# LPC_AP2_3_52.net
KiCad netlist of a schematic drawn in EAGLE
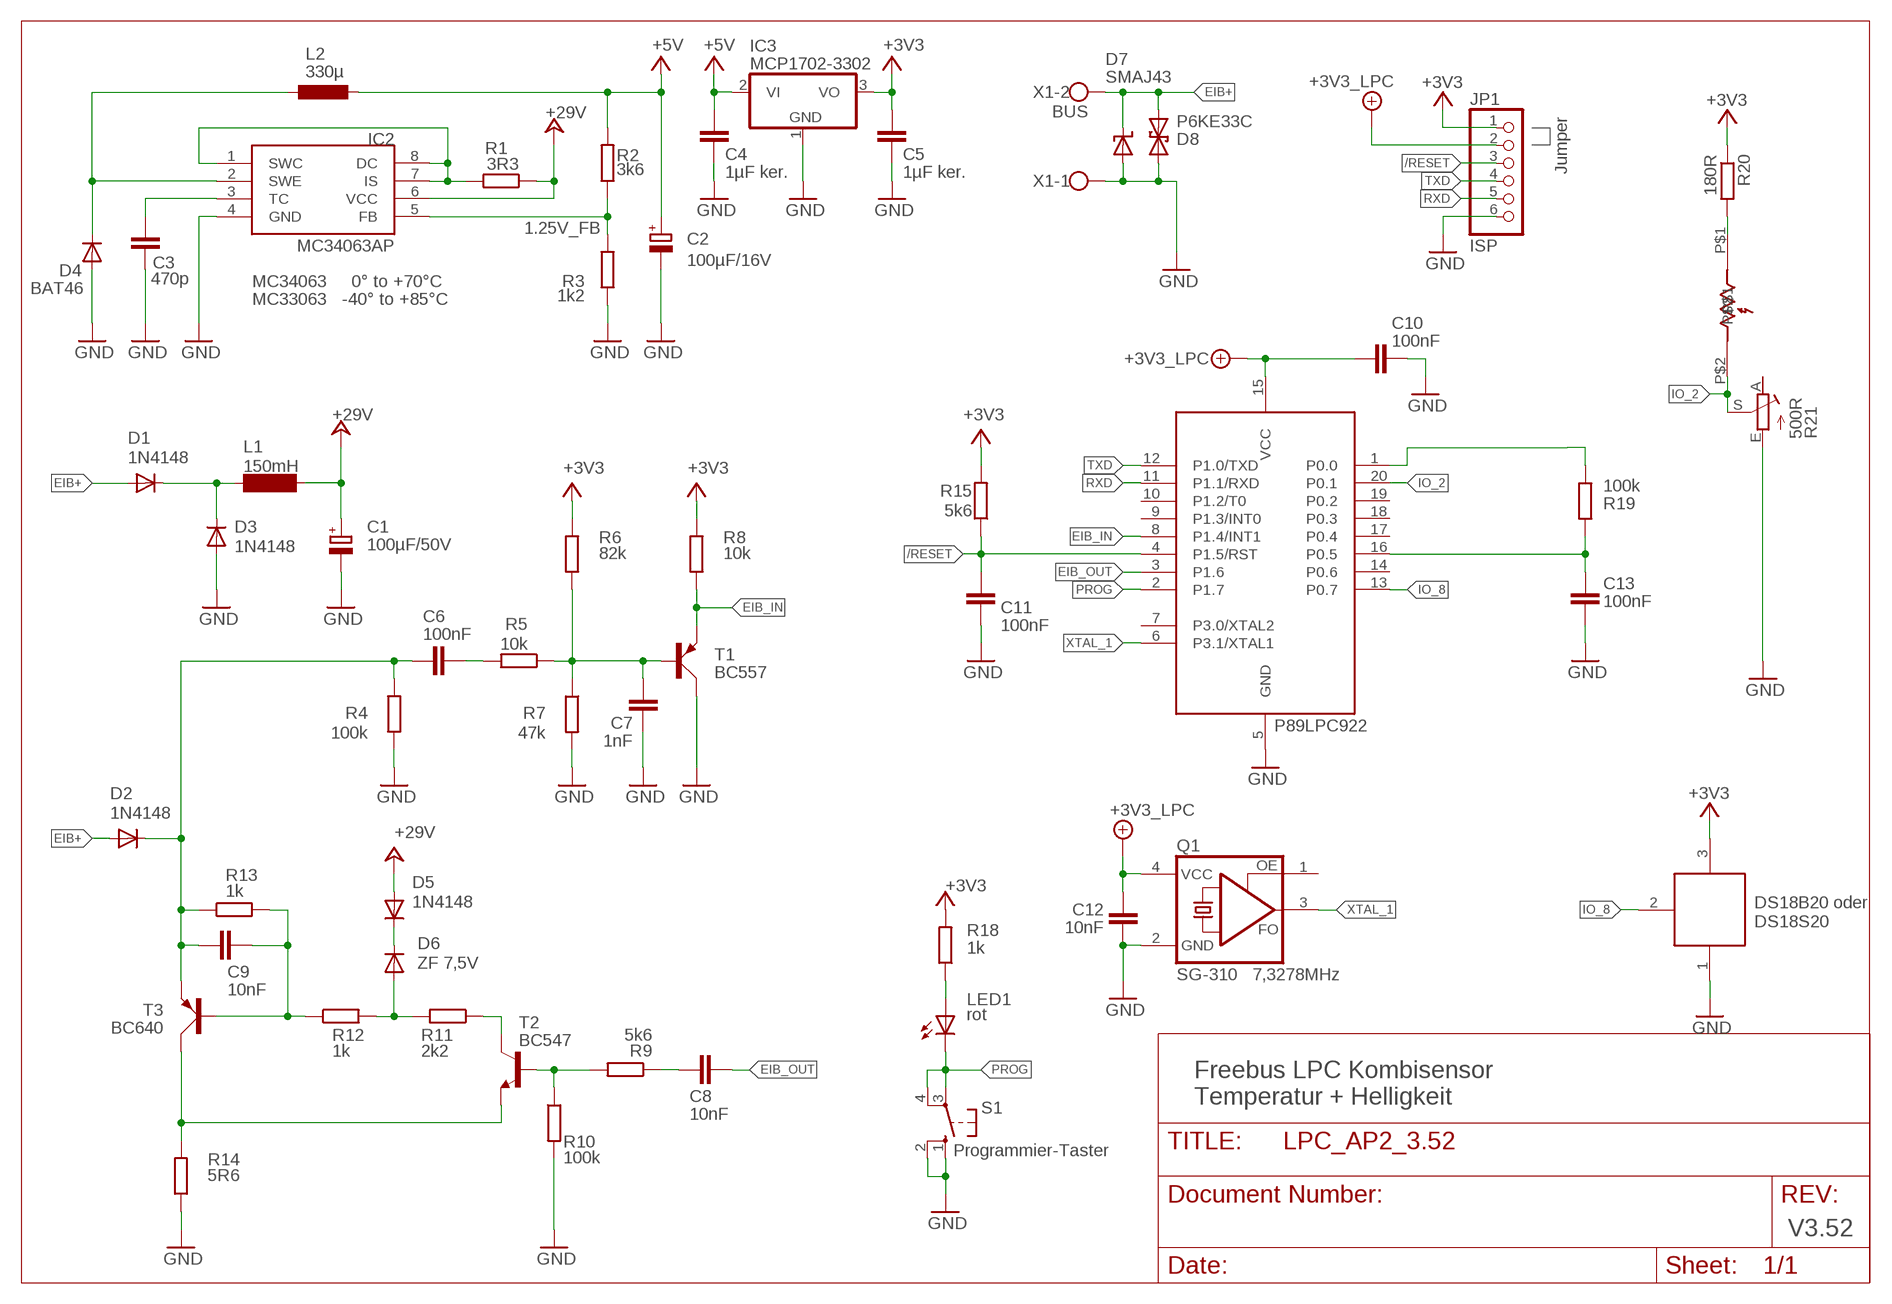
[diagram p0: schematic, sheet 1]

(export (version "E")
  (design (tool "Eeschema 10.0.6"))
  (components
    (comp (ref "C1")
      (value "100µF/50V")
      (footprint "eagle-import:E3,5-8")
      (libsource (lib "eagle-import") (part "CPOL-EUE3.5-8"))
    )
    (comp (ref "C2")
      (value "100µF/16V")
      (footprint "eagle-import:E2-5")
      (libsource (lib "eagle-import") (part "CPOL-EUE2-5"))
    )
    (comp (ref "C3")
      (value "470p")
      (footprint "eagle-import:C025-024X044")
      (libsource (lib "eagle-import") (part "C-EU025-024X044"))
    )
    (comp (ref "C4")
      (value "1µF ker.")
      (footprint "eagle-import:C050-024X044")
      (libsource (lib "eagle-import") (part "C-EU050-024X044"))
    )
    (comp (ref "C5")
      (value "1µF ker.")
      (footprint "eagle-import:C050-024X044")
      (libsource (lib "eagle-import") (part "C-EU050-024X044"))
    )
    (comp (ref "C6")
      (value "100nF")
      (footprint "eagle-import:C050-024X044")
      (libsource (lib "eagle-import") (part "C-EU050-024X044"))
    )
    (comp (ref "C7")
      (value "1nF")
      (footprint "eagle-import:C050-024X044")
      (libsource (lib "eagle-import") (part "C-EU050-024X044"))
    )
    (comp (ref "C8")
      (value "10nF")
      (footprint "eagle-import:C050-024X044")
      (libsource (lib "eagle-import") (part "C-EU050-024X044"))
    )
    (comp (ref "C9")
      (value "10nF")
      (footprint "eagle-import:C050-024X044")
      (libsource (lib "eagle-import") (part "C-EU050-024X044"))
    )
    (comp (ref "C10")
      (value "100nF")
      (footprint "eagle-import:C0805K")
      (libsource (lib "eagle-import") (part "C-EUC0805K"))
    )
    (comp (ref "C11")
      (value "100nF")
      (footprint "eagle-import:C050-024X044")
      (libsource (lib "eagle-import") (part "C-EU050-024X044"))
    )
    (comp (ref "C12")
      (value "10nF")
      (footprint "eagle-import:C0805K")
      (libsource (lib "eagle-import") (part "C-EUC0805K"))
    )
    (comp (ref "C13")
      (value "100nF")
      (footprint "eagle-import:C050-024X044")
      (libsource (lib "eagle-import") (part "C-EU050-024X044"))
    )
    (comp (ref "D1")
      (value "1N4148")
      (footprint "eagle-import:D-2.5")
      (libsource (lib "eagle-import") (part "DIODE-D-2.5"))
    )
    (comp (ref "D2")
      (value "1N4148")
      (footprint "eagle-import:DO35-7")
      (libsource (lib "eagle-import") (part "1N4148DO35-7"))
    )
    (comp (ref "D3")
      (value "1N4148")
      (footprint "eagle-import:D-2.5")
      (libsource (lib "eagle-import") (part "DIODE-D-2.5"))
    )
    (comp (ref "D4")
      (value "BAT46")
      (footprint "eagle-import:DO34-5R")
      (libsource (lib "eagle-import") (part "1N4148DO34-5R"))
    )
    (comp (ref "D5")
      (value "1N4148")
      (footprint "eagle-import:DO34-5R")
      (libsource (lib "eagle-import") (part "1N4148DO34-5R"))
    )
    (comp (ref "D6")
      (value "ZF 7,5V")
      (footprint "eagle-import:DO34-5R")
      (libsource (lib "eagle-import") (part "1N4148DO34-5R"))
    )
    (comp (ref "D7")
      (value "SMAJ43")
      (footprint "eagle-import:SMBJ")
      (libsource (lib "eagle-import") (part "SUPPRESSOR-SMBJ"))
    )
    (comp (ref "D8")
      (value "P6KE33C")
      (footprint "eagle-import:DO41-7")
      (libsource (lib "eagle-import") (part "P6KEXXCDO41-7"))
    )
    (comp (ref "IC1")
      (value "89LPC922FN")
      (footprint "eagle-import:DIL20")
      (libsource (lib "eagle-import") (part "89LPC922"))
    )
    (comp (ref "IC2")
      (value "MC34063AP")
      (footprint "eagle-import:DIL08")
      (libsource (lib "eagle-import") (part "MC34063AP"))
    )
    (comp (ref "IC3")
      (value "MCP1702-3302")
      (footprint "eagle-import:TO92")
      (libsource (lib "eagle-import") (part "MCP1703TO92"))
    )
    (comp (ref "IC4")
      (value "DS18X20")
      (footprint "eagle-import:DS18X")
      (libsource (lib "eagle-import") (part "DS18X"))
    )
    (comp (ref "JP1")
      (value "ISP")
      (footprint "eagle-import:1X06")
      (libsource (lib "eagle-import") (part "PINHD-1X6"))
    )
    (comp (ref "L1")
      (value "150mH")
      (footprint "eagle-import:SD12K100")
      (libsource (lib "eagle-import") (part "SD12K100"))
    )
    (comp (ref "L2")
      (value "330µ")
      (footprint "eagle-import:0207_7")
      (libsource (lib "eagle-import") (part "L-EU0207/7"))
    )
    (comp (ref "LDR1")
      (value "LDR07")
      (footprint "eagle-import:LDR07")
      (libsource (lib "eagle-import") (part "LDR07"))
    )
    (comp (ref "LED1")
      (value "rot")
      (footprint "eagle-import:LED3MM")
      (libsource (lib "eagle-import") (part "LED3MM"))
    )
    (comp (ref "Q1")
      (value "SG-310 7,3278MHz")
      (footprint "eagle-import:ASF")
      (libsource (lib "eagle-import") (part "ASF1"))
    )
    (comp (ref "R1")
      (value "3R3")
      (footprint "eagle-import:0207_2V")
      (libsource (lib "eagle-import") (part "R-EU_0207/2V"))
    )
    (comp (ref "R2")
      (value "3k6")
      (footprint "eagle-import:0207_2V")
      (libsource (lib "eagle-import") (part "R-EU_0207/2V"))
    )
    (comp (ref "R3")
      (value "1k2")
      (footprint "eagle-import:0207_2V")
      (libsource (lib "eagle-import") (part "R-EU_0207/2V"))
    )
    (comp (ref "R4")
      (value "100k")
      (footprint "eagle-import:0207_2V")
      (libsource (lib "eagle-import") (part "R-EU_0207/2V"))
    )
    (comp (ref "R5")
      (value "10k")
      (footprint "eagle-import:0207_2V")
      (libsource (lib "eagle-import") (part "R-EU_0207/2V"))
    )
    (comp (ref "R6")
      (value "82k")
      (footprint "eagle-import:0207_2V")
      (libsource (lib "eagle-import") (part "R-EU_0207/2V"))
    )
    (comp (ref "R7")
      (value "47k")
      (footprint "eagle-import:0207_2V")
      (libsource (lib "eagle-import") (part "R-EU_0207/2V"))
    )
    (comp (ref "R8")
      (value "10k")
      (footprint "eagle-import:0207_2V")
      (libsource (lib "eagle-import") (part "R-EU_0207/2V"))
    )
    (comp (ref "R9")
      (value "5k6")
      (footprint "eagle-import:0207_2V")
      (libsource (lib "eagle-import") (part "R-EU_0207/2V"))
    )
    (comp (ref "R10")
      (value "100k")
      (footprint "eagle-import:0207_2V")
      (libsource (lib "eagle-import") (part "R-EU_0207/2V"))
    )
    (comp (ref "R11")
      (value "2k2")
      (footprint "eagle-import:0207_2V")
      (libsource (lib "eagle-import") (part "R-EU_0207/2V"))
    )
    (comp (ref "R12")
      (value "1k")
      (footprint "eagle-import:0207_2V")
      (libsource (lib "eagle-import") (part "R-EU_0207/2V"))
    )
    (comp (ref "R13")
      (value "1k")
      (footprint "eagle-import:0207_7")
      (libsource (lib "eagle-import") (part "R-EU_0207/7"))
    )
    (comp (ref "R14")
      (value "5R6")
      (footprint "eagle-import:0207_2V")
      (libsource (lib "eagle-import") (part "R-EU_0207/2V"))
    )
    (comp (ref "R15")
      (value "5k6")
      (footprint "eagle-import:0207_2V")
      (libsource (lib "eagle-import") (part "R-EU_0207/2V"))
    )
    (comp (ref "R18")
      (value "1k")
      (footprint "eagle-import:0207_7")
      (libsource (lib "eagle-import") (part "R-EU_0207/7"))
    )
    (comp (ref "R19")
      (value "100k")
      (footprint "eagle-import:0207_7")
      (libsource (lib "eagle-import") (part "R-EU_0207/7"))
    )
    (comp (ref "R20")
      (value "180R")
      (footprint "eagle-import:0207_2V")
      (libsource (lib "eagle-import") (part "R-EU_0207/2V"))
    )
    (comp (ref "R21")
      (value "500R")
      (footprint "eagle-import:PT6L")
      (libsource (lib "eagle-import") (part "R-TRIMM-PT6L"))
    )
    (comp (ref "S1")
      (value "Programmier-Taster")
      (footprint "eagle-import:B3F-10XX")
      (fields (field (name "MPN") "B3F-1000"))
      (libsource (lib "eagle-import") (part "10-XX"))
    )
    (comp (ref "T1")
      (value "BC557")
      (footprint "eagle-import:SOT54A")
      (libsource (lib "eagle-import") (part "BC557"))
    )
    (comp (ref "T2")
      (value "BC547")
      (footprint "eagle-import:TO92")
      (libsource (lib "eagle-import") (part "BC547"))
    )
    (comp (ref "T3")
      (value "BC640")
      (footprint "eagle-import:SOT54D")
      (libsource (lib "eagle-import") (part "BC640"))
    )
    (comp (ref "X1")
      (value "BUS")
      (footprint "eagle-import:W237-132")
      (libsource (lib "eagle-import") (part "W237-02P"))
    )
  )
  (nets
    (net (code "1") (name "+3V3") (class "Default")
      (node (ref "C5") (pin "1") (pinfunction "1_1") (pintype "passive"))
      (node (ref "IC3") (pin "3") (pinfunction "VO_3") (pintype "passive"))
      (node (ref "IC4") (pin "3") (pinfunction "VDD_3") (pintype "power_in"))
      (node (ref "JP1") (pin "1") (pinfunction "1_1") (pintype "passive"))
      (node (ref "R15") (pin "2") (pinfunction "2_2") (pintype "passive"))
      (node (ref "R18") (pin "2") (pinfunction "2_2") (pintype "passive"))
      (node (ref "R20") (pin "1") (pinfunction "1_1") (pintype "passive"))
      (node (ref "R6") (pin "2") (pinfunction "2_2") (pintype "passive"))
      (node (ref "R8") (pin "2") (pinfunction "2_2") (pintype "passive"))
    )
    (net (code "2") (name "+3V3_LPC") (class "Default")
      (node (ref "C10") (pin "2") (pinfunction "2_2") (pintype "passive"))
      (node (ref "C12") (pin "1") (pinfunction "1_1") (pintype "passive"))
      (node (ref "IC1") (pin "15") (pinfunction "VCC_15") (pintype "bidirectional"))
      (node (ref "JP1") (pin "2") (pinfunction "2_2") (pintype "passive"))
      (node (ref "Q1") (pin "4") (pinfunction "VCC_4") (pintype "power_in"))
    )
    (net (code "3") (name "+5V") (class "Default")
      (node (ref "C2") (pin "+") (pinfunction "+_+") (pintype "passive"))
      (node (ref "C4") (pin "1") (pinfunction "1_1") (pintype "passive"))
      (node (ref "IC3") (pin "2") (pinfunction "VI_2") (pintype "input"))
      (node (ref "L2") (pin "1") (pinfunction "1_1") (pintype "passive"))
      (node (ref "R2") (pin "2") (pinfunction "2_2") (pintype "passive"))
    )
    (net (code "4") (name "+29V") (class "Default")
      (node (ref "C1") (pin "+") (pinfunction "+_+") (pintype "passive"))
      (node (ref "D5") (pin "A") (pinfunction "A_A") (pintype "passive"))
      (node (ref "IC2") (pin "6") (pinfunction "VCC_6") (pintype "passive"))
      (node (ref "L1") (pin "2") (pinfunction "2_2") (pintype "passive"))
      (node (ref "R1") (pin "1") (pinfunction "1_1") (pintype "passive"))
    )
    (net (code "5") (name "/1.25V_FB") (class "Default")
      (node (ref "IC2") (pin "5") (pinfunction "FB_5") (pintype "passive"))
      (node (ref "R2") (pin "1") (pinfunction "1_1") (pintype "passive"))
      (node (ref "R3") (pin "2") (pinfunction "2_2") (pintype "passive"))
    )
    (net (code "6") (name "EIB+") (class "Default")
      (node (ref "D1") (pin "A") (pinfunction "A_A") (pintype "passive"))
      (node (ref "D2") (pin "A") (pinfunction "A_A") (pintype "passive"))
      (node (ref "D7") (pin "C") (pinfunction "C_C") (pintype "passive"))
      (node (ref "D8") (pin "C") (pinfunction "2_C") (pintype "passive"))
      (node (ref "X1") (pin "2") (pinfunction "KL_2") (pintype "passive"))
    )
    (net (code "7") (name "EIB_IN") (class "Default")
      (node (ref "IC1") (pin "8") (pinfunction "P1.4/INT1_8") (pintype "bidirectional"))
      (node (ref "R8") (pin "1") (pinfunction "1_1") (pintype "passive"))
      (node (ref "T1") (pin "E") (pinfunction "E_E") (pintype "passive"))
    )
    (net (code "8") (name "EIB_OUT") (class "Default")
      (node (ref "C8") (pin "2") (pinfunction "2_2") (pintype "passive"))
      (node (ref "IC1") (pin "3") (pinfunction "P1.6_3") (pintype "bidirectional"))
    )
    (net (code "9") (name "GND") (class "Default")
      (node (ref "C1") (pin "-") (pinfunction "-_-") (pintype "passive"))
      (node (ref "C10") (pin "1") (pinfunction "1_1") (pintype "passive"))
      (node (ref "C11") (pin "1") (pinfunction "1_1") (pintype "passive"))
      (node (ref "C12") (pin "2") (pinfunction "2_2") (pintype "passive"))
      (node (ref "C13") (pin "1") (pinfunction "1_1") (pintype "passive"))
      (node (ref "C2") (pin "-") (pinfunction "-_-") (pintype "passive"))
      (node (ref "C3") (pin "1") (pinfunction "1_1") (pintype "passive"))
      (node (ref "C4") (pin "2") (pinfunction "2_2") (pintype "passive"))
      (node (ref "C5") (pin "2") (pinfunction "2_2") (pintype "passive"))
      (node (ref "C7") (pin "1") (pinfunction "1_1") (pintype "passive"))
      (node (ref "D3") (pin "A") (pinfunction "A_A") (pintype "passive"))
      (node (ref "D4") (pin "A") (pinfunction "A_A") (pintype "passive"))
      (node (ref "D7") (pin "A") (pinfunction "A_A") (pintype "passive"))
      (node (ref "D8") (pin "A") (pinfunction "1_A") (pintype "passive"))
      (node (ref "IC1") (pin "5") (pinfunction "GND_5") (pintype "bidirectional"))
      (node (ref "IC2") (pin "4") (pinfunction "GND_4") (pintype "passive"))
      (node (ref "IC3") (pin "1") (pinfunction "GND_1") (pintype "passive"))
      (node (ref "IC4") (pin "1") (pinfunction "GND_1") (pintype "power_in"))
      (node (ref "JP1") (pin "6") (pinfunction "6_6") (pintype "passive"))
      (node (ref "Q1") (pin "2") (pinfunction "GND_2") (pintype "power_in"))
      (node (ref "R10") (pin "2") (pinfunction "2_2") (pintype "passive"))
      (node (ref "R14") (pin "1") (pinfunction "1_1") (pintype "passive"))
      (node (ref "R21") (pin "E") (pinfunction "E_E") (pintype "passive"))
      (node (ref "R3") (pin "1") (pinfunction "1_1") (pintype "passive"))
      (node (ref "R4") (pin "1") (pinfunction "1_1") (pintype "passive"))
      (node (ref "R7") (pin "2") (pinfunction "2_2") (pintype "passive"))
      (node (ref "S1") (pin "1") (pinfunction "S_1") (pintype "passive"))
      (node (ref "S1") (pin "2") (pinfunction "S1_2") (pintype "passive"))
      (node (ref "T1") (pin "C") (pinfunction "C_C") (pintype "passive"))
      (node (ref "X1") (pin "1") (pinfunction "KL_1") (pintype "passive"))
    )
    (net (code "10") (name "IO_2") (class "Default")
      (node (ref "IC1") (pin "20") (pinfunction "P0.1_20") (pintype "bidirectional"))
      (node (ref "LDR1") (pin "P$2") (pinfunction "P$2_P$2") (pintype "bidirectional"))
      (node (ref "R21") (pin "S") (pinfunction "S_S") (pintype "passive"))
    )
    (net (code "11") (name "IO_8") (class "Default")
      (node (ref "IC1") (pin "13") (pinfunction "P0.7_13") (pintype "bidirectional"))
      (node (ref "IC4") (pin "2") (pinfunction "IO_2") (pintype "bidirectional"))
    )
    (net (code "12") (name "Net-(C6-Pad1)") (class "Default")
      (node (ref "C6") (pin "1") (pinfunction "1_1") (pintype "passive"))
      (node (ref "C9") (pin "1") (pinfunction "1_1") (pintype "passive"))
      (node (ref "D2") (pin "C") (pinfunction "C_C") (pintype "passive"))
      (node (ref "R13") (pin "1") (pinfunction "1_1") (pintype "passive"))
      (node (ref "R4") (pin "2") (pinfunction "2_2") (pintype "passive"))
      (node (ref "T3") (pin "E") (pinfunction "E_E") (pintype "passive"))
    )
    (net (code "13") (name "Net-(C6-Pad2)") (class "Default")
      (node (ref "C6") (pin "2") (pinfunction "2_2") (pintype "passive"))
      (node (ref "R5") (pin "2") (pinfunction "2_2") (pintype "passive"))
    )
    (net (code "14") (name "Net-(C7-Pad2)") (class "Default")
      (node (ref "C7") (pin "2") (pinfunction "2_2") (pintype "passive"))
      (node (ref "R5") (pin "1") (pinfunction "1_1") (pintype "passive"))
      (node (ref "R6") (pin "1") (pinfunction "1_1") (pintype "passive"))
      (node (ref "R7") (pin "1") (pinfunction "1_1") (pintype "passive"))
      (node (ref "T1") (pin "B") (pinfunction "B_B") (pintype "passive"))
    )
    (net (code "15") (name "Net-(C8-Pad1)") (class "Default")
      (node (ref "C8") (pin "1") (pinfunction "1_1") (pintype "passive"))
      (node (ref "R9") (pin "1") (pinfunction "1_1") (pintype "passive"))
    )
    (net (code "16") (name "Net-(C9-Pad2)") (class "Default")
      (node (ref "C9") (pin "2") (pinfunction "2_2") (pintype "passive"))
      (node (ref "R12") (pin "1") (pinfunction "1_1") (pintype "passive"))
      (node (ref "R13") (pin "2") (pinfunction "2_2") (pintype "passive"))
      (node (ref "T3") (pin "B") (pinfunction "B_B") (pintype "passive"))
    )
    (net (code "17") (name "Net-(D1-PadC)") (class "Default")
      (node (ref "D1") (pin "C") (pinfunction "C_C") (pintype "passive"))
      (node (ref "D3") (pin "C") (pinfunction "C_C") (pintype "passive"))
      (node (ref "L1") (pin "1") (pinfunction "1_1") (pintype "passive"))
    )
    (net (code "18") (name "Net-(D5-PadC)") (class "Default")
      (node (ref "D5") (pin "C") (pinfunction "C_C") (pintype "passive"))
      (node (ref "D6") (pin "C") (pinfunction "C_C") (pintype "passive"))
    )
    (net (code "19") (name "Net-(D6-PadA)") (class "Default")
      (node (ref "D6") (pin "A") (pinfunction "A_A") (pintype "passive"))
      (node (ref "R11") (pin "2") (pinfunction "2_2") (pintype "passive"))
      (node (ref "R12") (pin "2") (pinfunction "2_2") (pintype "passive"))
    )
    (net (code "20") (name "Net-(IC1-P0.0)") (class "Default")
      (node (ref "IC1") (pin "1") (pinfunction "P0.0_1") (pintype "bidirectional"))
      (node (ref "R19") (pin "1") (pinfunction "1_1") (pintype "passive"))
    )
    (net (code "21") (name "Net-(IC1-P0.5)") (class "Default")
      (node (ref "C13") (pin "2") (pinfunction "2_2") (pintype "passive"))
      (node (ref "IC1") (pin "16") (pinfunction "P0.5_16") (pintype "bidirectional"))
      (node (ref "R19") (pin "2") (pinfunction "2_2") (pintype "passive"))
    )
    (net (code "22") (name "Net-(IC2-DC)") (class "Default")
      (node (ref "IC2") (pin "1") (pinfunction "SWC_1") (pintype "passive"))
      (node (ref "IC2") (pin "7") (pinfunction "IS_7") (pintype "passive"))
      (node (ref "IC2") (pin "8") (pinfunction "DC_8") (pintype "passive"))
      (node (ref "R1") (pin "2") (pinfunction "2_2") (pintype "passive"))
    )
    (net (code "23") (name "Net-(IC2-SWE)") (class "Default")
      (node (ref "D4") (pin "C") (pinfunction "C_C") (pintype "passive"))
      (node (ref "IC2") (pin "2") (pinfunction "SWE_2") (pintype "passive"))
      (node (ref "L2") (pin "2") (pinfunction "2_2") (pintype "passive"))
    )
    (net (code "24") (name "Net-(IC2-TC)") (class "Default")
      (node (ref "C3") (pin "2") (pinfunction "2_2") (pintype "passive"))
      (node (ref "IC2") (pin "3") (pinfunction "TC_3") (pintype "passive"))
    )
    (net (code "25") (name "Net-(LDR1-PadP$1)") (class "Default")
      (node (ref "LDR1") (pin "P$1") (pinfunction "P$1_P$1") (pintype "bidirectional"))
      (node (ref "R20") (pin "2") (pinfunction "2_2") (pintype "passive"))
    )
    (net (code "26") (name "Net-(LED1-PadA)") (class "Default")
      (node (ref "LED1") (pin "A") (pinfunction "A_A") (pintype "passive"))
      (node (ref "R18") (pin "1") (pinfunction "1_1") (pintype "passive"))
    )
    (net (code "27") (name "Net-(T2-B)") (class "Default")
      (node (ref "R10") (pin "1") (pinfunction "1_1") (pintype "passive"))
      (node (ref "R9") (pin "2") (pinfunction "2_2") (pintype "passive"))
      (node (ref "T2") (pin "2") (pinfunction "B_2") (pintype "passive"))
    )
    (net (code "28") (name "Net-(T2-C)") (class "Default")
      (node (ref "R11") (pin "1") (pinfunction "1_1") (pintype "passive"))
      (node (ref "T2") (pin "3") (pinfunction "C_3") (pintype "passive"))
    )
    (net (code "29") (name "Net-(T2-E)") (class "Default")
      (node (ref "R14") (pin "2") (pinfunction "2_2") (pintype "passive"))
      (node (ref "T2") (pin "1") (pinfunction "E_1") (pintype "passive"))
      (node (ref "T3") (pin "C") (pinfunction "C_C") (pintype "passive"))
    )
    (net (code "30") (name "PROG") (class "Default")
      (node (ref "IC1") (pin "2") (pinfunction "P1.7_2") (pintype "bidirectional"))
      (node (ref "LED1") (pin "K") (pinfunction "C_K") (pintype "passive"))
      (node (ref "S1") (pin "3") (pinfunction "P_3") (pintype "passive"))
      (node (ref "S1") (pin "4") (pinfunction "P1_4") (pintype "passive"))
    )
    (net (code "31") (name "RXD") (class "Default")
      (node (ref "IC1") (pin "11") (pinfunction "P1.1/RXD_11") (pintype "bidirectional"))
      (node (ref "JP1") (pin "5") (pinfunction "5_5") (pintype "passive"))
    )
    (net (code "32") (name "TXD") (class "Default")
      (node (ref "IC1") (pin "12") (pinfunction "P1.0/TXD_12") (pintype "bidirectional"))
      (node (ref "JP1") (pin "4") (pinfunction "4_4") (pintype "passive"))
    )
    (net (code "33") (name "XTAL_1") (class "Default")
      (node (ref "IC1") (pin "6") (pinfunction "P3.1/XTAL1_6") (pintype "bidirectional"))
      (node (ref "Q1") (pin "3") (pinfunction "FO_3") (pintype "output"))
    )
    (net (code "34") (name "unconnected-(IC1-P0.2-Pad19)") (class "Default")
      (node (ref "IC1") (pin "19") (pinfunction "P0.2_19") (pintype "bidirectional"))
    )
    (net (code "35") (name "unconnected-(IC1-P0.3-Pad18)") (class "Default")
      (node (ref "IC1") (pin "18") (pinfunction "P0.3_18") (pintype "bidirectional"))
    )
    (net (code "36") (name "unconnected-(IC1-P0.4-Pad17)") (class "Default")
      (node (ref "IC1") (pin "17") (pinfunction "P0.4_17") (pintype "bidirectional"))
    )
    (net (code "37") (name "unconnected-(IC1-P0.6-Pad14)") (class "Default")
      (node (ref "IC1") (pin "14") (pinfunction "P0.6_14") (pintype "bidirectional"))
    )
    (net (code "38") (name "unconnected-(IC1-P1.2{slash}T0-Pad10)") (class "Default")
      (node (ref "IC1") (pin "10") (pinfunction "P1.2/T0_10") (pintype "bidirectional"))
    )
    (net (code "39") (name "unconnected-(IC1-P1.3{slash}INT0-Pad9)") (class "Default")
      (node (ref "IC1") (pin "9") (pinfunction "P1.3/INT0_9") (pintype "bidirectional"))
    )
    (net (code "40") (name "unconnected-(IC1-P3.0{slash}XTAL2-Pad7)") (class "Default")
      (node (ref "IC1") (pin "7") (pinfunction "P3.0/XTAL2_7") (pintype "bidirectional"))
    )
    (net (code "41") (name "unconnected-(Q1-OE-Pad1)") (class "Default")
      (node (ref "Q1") (pin "1") (pinfunction "OE_1") (pintype "input"))
    )
    (net (code "42") (name "unconnected-(R21-PadA)") (class "Default")
      (node (ref "R21") (pin "A") (pinfunction "A_A") (pintype "passive"))
    )
    (net (code "43") (name "{slash}RESET") (class "Default")
      (node (ref "C11") (pin "2") (pinfunction "2_2") (pintype "passive"))
      (node (ref "IC1") (pin "4") (pinfunction "P1.5/RST_4") (pintype "bidirectional"))
      (node (ref "JP1") (pin "3") (pinfunction "3_3") (pintype "passive"))
      (node (ref "R15") (pin "1") (pinfunction "1_1") (pintype "passive"))
    )
  )
)
